# MaUWB_DSTO_v1_0.net
KiCad netlist of a schematic drawn in EAGLE
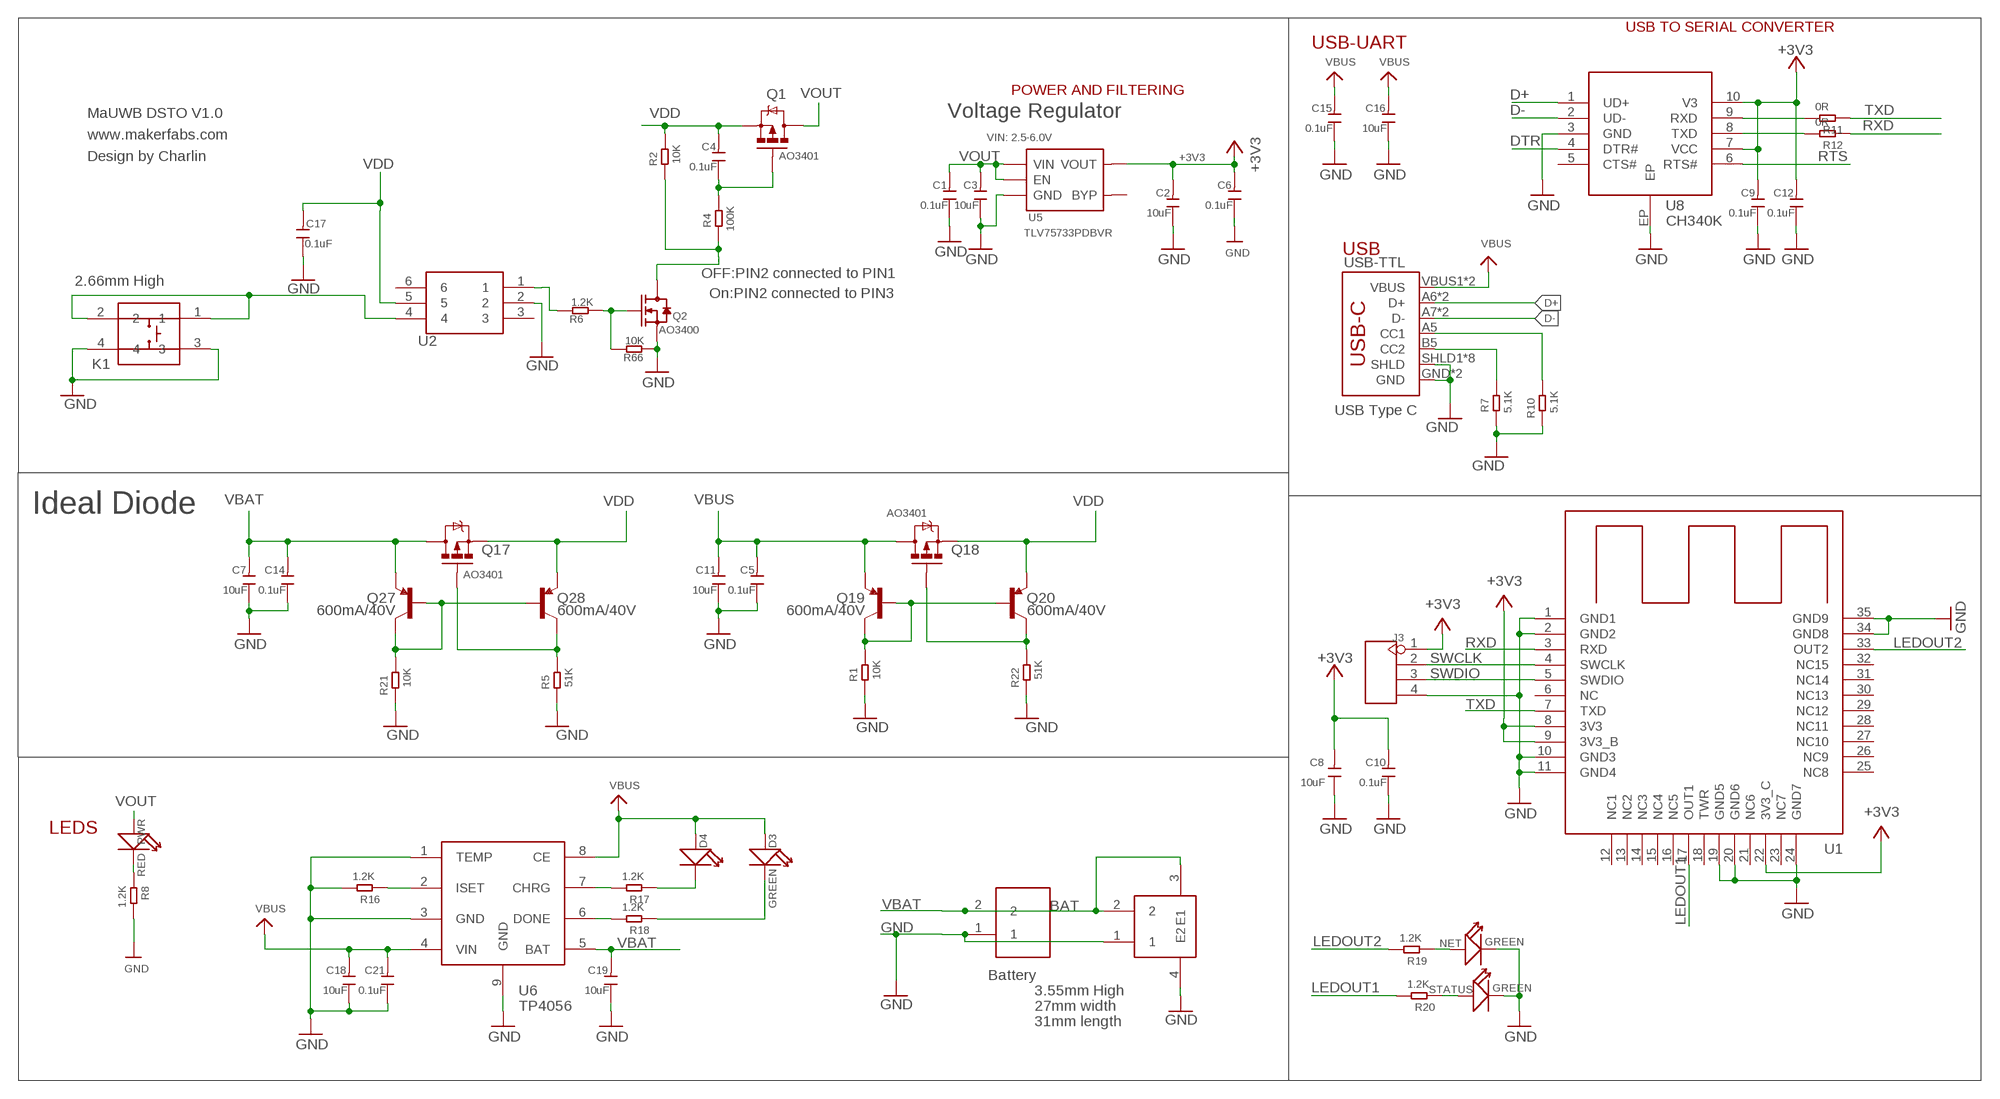
[diagram p0: schematic, sheet 1]

(export (version "E")
  (design (tool "Eeschema 10.0.6"))
  (components
    (comp (ref "BAT")
      (value "PH2.0-2P-90-DIP")
      (footprint "eagle-import:PH2.0-2P-90-DIP")
      (libsource (lib "eagle-import") (part "PH2.0-2P-90-DIP"))
    )
    (comp (ref "C1")
      (value "0.1uF")
      (footprint "eagle-import:DISCRETE_C0402")
      (libsource (lib "eagle-import") (part "DISCRETE_C-0402"))
    )
    (comp (ref "C2")
      (value "10uF")
      (footprint "eagle-import:DISCRETE_C0402")
      (libsource (lib "eagle-import") (part "DISCRETE_C-0402"))
    )
    (comp (ref "C3")
      (value "10uF")
      (footprint "eagle-import:DISCRETE_C0402")
      (libsource (lib "eagle-import") (part "DISCRETE_C-0402"))
    )
    (comp (ref "C4")
      (value "0.1uF")
      (footprint "eagle-import:DISCRETE_C0402")
      (libsource (lib "eagle-import") (part "DISCRETE_C-0402"))
    )
    (comp (ref "C5")
      (value "0.1uF")
      (footprint "eagle-import:DISCRETE_C0402")
      (libsource (lib "eagle-import") (part "DISCRETE_C-0402"))
    )
    (comp (ref "C6")
      (value "0.1uF")
      (footprint "eagle-import:DISCRETE_C0402")
      (libsource (lib "eagle-import") (part "DISCRETE_C-0402"))
    )
    (comp (ref "C7")
      (value "10uF")
      (footprint "eagle-import:DISCRETE_C0402")
      (libsource (lib "eagle-import") (part "DISCRETE_C-0402"))
    )
    (comp (ref "C8")
      (value "10uF")
      (footprint "eagle-import:DISCRETE_C0402")
      (libsource (lib "eagle-import") (part "DISCRETE_C-0402"))
    )
    (comp (ref "C9")
      (value "0.1uF")
      (footprint "eagle-import:DISCRETE_C0402")
      (libsource (lib "eagle-import") (part "DISCRETE_C-0402"))
    )
    (comp (ref "C10")
      (value "0.1uF")
      (footprint "eagle-import:DISCRETE_C0402")
      (libsource (lib "eagle-import") (part "DISCRETE_C-0402"))
    )
    (comp (ref "C11")
      (value "10uF")
      (footprint "eagle-import:DISCRETE_C0402")
      (libsource (lib "eagle-import") (part "DISCRETE_C-0402"))
    )
    (comp (ref "C12")
      (value "0.1uF")
      (footprint "eagle-import:DISCRETE_C0402")
      (libsource (lib "eagle-import") (part "DISCRETE_C-0402"))
    )
    (comp (ref "C14")
      (value "0.1uF")
      (footprint "eagle-import:DISCRETE_C0402")
      (libsource (lib "eagle-import") (part "DISCRETE_C-0402"))
    )
    (comp (ref "C15")
      (value "0.1uF")
      (footprint "eagle-import:DISCRETE_C0402")
      (libsource (lib "eagle-import") (part "DISCRETE_C-0402"))
    )
    (comp (ref "C16")
      (value "10uF")
      (footprint "eagle-import:DISCRETE_C0402")
      (libsource (lib "eagle-import") (part "DISCRETE_C-0402"))
    )
    (comp (ref "C17")
      (value "0.1uF")
      (footprint "eagle-import:DISCRETE_C0402")
      (libsource (lib "eagle-import") (part "DISCRETE_C-0402"))
    )
    (comp (ref "C18")
      (value "10uF")
      (footprint "eagle-import:DISCRETE_C0402")
      (libsource (lib "eagle-import") (part "DISCRETE_C-0402"))
    )
    (comp (ref "C19")
      (value "10uF")
      (footprint "eagle-import:DISCRETE_C0402")
      (libsource (lib "eagle-import") (part "DISCRETE_C-0402"))
    )
    (comp (ref "C21")
      (value "0.1uF")
      (footprint "eagle-import:DISCRETE_C0402")
      (libsource (lib "eagle-import") (part "DISCRETE_C-0402"))
    )
    (comp (ref "D3")
      (value "GREEN")
      (footprint "eagle-import:DISCRETE_LED-0603")
      (libsource (lib "eagle-import") (part "DISCRETE_LED0603"))
    )
    (comp (ref "D4")
      (value "DISCRETE_LED0603")
      (footprint "eagle-import:DISCRETE_LED-0603")
      (libsource (lib "eagle-import") (part "DISCRETE_LED0603"))
    )
    (comp (ref "J2")
      (value "JST-ACH1.2-2P")
      (footprint "eagle-import:A1203WRS-2P")
      (libsource (lib "eagle-import") (part "JST-ACH1.2-2P"))
    )
    (comp (ref "J3")
      (value "HEADER-4P-60/35MILROUND")
      (footprint "eagle-import:4P-65_35ROUND")
      (libsource (lib "eagle-import") (part "HEADER-4P-60/35MILROUND"))
    )
    (comp (ref "K1")
      (value "BTN01A")
      (footprint "eagle-import:BTN01A")
      (libsource (lib "eagle-import") (part "BTN01A"))
    )
    (comp (ref "NET")
      (value "GREEN")
      (footprint "eagle-import:DISCRETE_LED-0603")
      (libsource (lib "eagle-import") (part "DISCRETE_LED0603"))
    )
    (comp (ref "PWR")
      (value "RED")
      (footprint "eagle-import:DISCRETE_LED-0603")
      (libsource (lib "eagle-import") (part "DISCRETE_LED0603"))
    )
    (comp (ref "Q1")
      (value "AO3401")
      (footprint "eagle-import:SOT23-3")
      (fields (field (name "PROD_ID") "TRANS-08285"))
      (libsource (lib "eagle-import") (part "MOSFET-PCHANNEL"))
    )
    (comp (ref "Q2")
      (value "AO3400")
      (footprint "eagle-import:SOT23@1")
      (libsource (lib "eagle-import") (part "MOSFET-N'SOT23'"))
    )
    (comp (ref "Q17")
      (value "AO3401")
      (footprint "eagle-import:SOT23-3")
      (fields (field (name "PROD_ID") "TRANS-08285"))
      (libsource (lib "eagle-import") (part "MOSFET-PCHANNEL"))
    )
    (comp (ref "Q18")
      (value "AO3401")
      (footprint "eagle-import:SOT23-3")
      (fields (field (name "PROD_ID") "TRANS-08285"))
      (libsource (lib "eagle-import") (part "MOSFET-PCHANNEL"))
    )
    (comp (ref "Q19")
      (value "600mA/40V")
      (footprint "eagle-import:SOT23-3")
      (libsource (lib "eagle-import") (part "TRANS_PNP-MMBT4403"))
    )
    (comp (ref "Q20")
      (value "600mA/40V")
      (footprint "eagle-import:SOT23-3")
      (fields (field (name "PROD_ID") "TRANS-09245"))
      (libsource (lib "eagle-import") (part "TRANS_PNP-MMBT4403"))
    )
    (comp (ref "Q27")
      (value "600mA/40V")
      (footprint "eagle-import:SOT23-3")
      (libsource (lib "eagle-import") (part "TRANS_PNP-MMBT4403"))
    )
    (comp (ref "Q28")
      (value "600mA/40V")
      (footprint "eagle-import:SOT23-3")
      (fields (field (name "PROD_ID") "TRANS-09245"))
      (libsource (lib "eagle-import") (part "TRANS_PNP-MMBT4403"))
    )
    (comp (ref "R1")
      (value "10K")
      (footprint "eagle-import:DISCRETE_R0402")
      (libsource (lib "eagle-import") (part "DISCRETE_R-0402"))
    )
    (comp (ref "R2")
      (value "10K")
      (footprint "eagle-import:DISCRETE_R0402")
      (libsource (lib "eagle-import") (part "DISCRETE_R-0402"))
    )
    (comp (ref "R4")
      (value "100K")
      (footprint "eagle-import:DISCRETE_R0402")
      (libsource (lib "eagle-import") (part "DISCRETE_R-0402"))
    )
    (comp (ref "R5")
      (value "51K")
      (footprint "eagle-import:DISCRETE_R0402")
      (libsource (lib "eagle-import") (part "DISCRETE_R-0402"))
    )
    (comp (ref "R6")
      (value "1.2K")
      (footprint "eagle-import:DISCRETE_R0402")
      (libsource (lib "eagle-import") (part "DISCRETE_R-0402"))
    )
    (comp (ref "R7")
      (value "5.1K")
      (footprint "eagle-import:DISCRETE_R0402")
      (libsource (lib "eagle-import") (part "DISCRETE_R-0402"))
    )
    (comp (ref "R8")
      (value "1.2K")
      (footprint "eagle-import:DISCRETE_R0402")
      (libsource (lib "eagle-import") (part "DISCRETE_R-0402"))
    )
    (comp (ref "R10")
      (value "5.1K")
      (footprint "eagle-import:DISCRETE_R0402")
      (libsource (lib "eagle-import") (part "DISCRETE_R-0402"))
    )
    (comp (ref "R11")
      (value "0R")
      (footprint "eagle-import:DISCRETE_R0402")
      (libsource (lib "eagle-import") (part "DISCRETE_R-0402"))
    )
    (comp (ref "R12")
      (value "0R")
      (footprint "eagle-import:DISCRETE_R0402")
      (libsource (lib "eagle-import") (part "DISCRETE_R-0402"))
    )
    (comp (ref "R16")
      (value "1.2K")
      (footprint "eagle-import:DISCRETE_R0402")
      (libsource (lib "eagle-import") (part "DISCRETE_R-0402"))
    )
    (comp (ref "R17")
      (value "1.2K")
      (footprint "eagle-import:DISCRETE_R0402")
      (libsource (lib "eagle-import") (part "DISCRETE_R-0402"))
    )
    (comp (ref "R18")
      (value "1.2K")
      (footprint "eagle-import:DISCRETE_R0402")
      (libsource (lib "eagle-import") (part "DISCRETE_R-0402"))
    )
    (comp (ref "R19")
      (value "1.2K")
      (footprint "eagle-import:DISCRETE_R0402")
      (libsource (lib "eagle-import") (part "DISCRETE_R-0402"))
    )
    (comp (ref "R20")
      (value "1.2K")
      (footprint "eagle-import:DISCRETE_R0402")
      (libsource (lib "eagle-import") (part "DISCRETE_R-0402"))
    )
    (comp (ref "R21")
      (value "10K")
      (footprint "eagle-import:DISCRETE_R0402")
      (libsource (lib "eagle-import") (part "DISCRETE_R-0402"))
    )
    (comp (ref "R22")
      (value "51K")
      (footprint "eagle-import:DISCRETE_R0402")
      (libsource (lib "eagle-import") (part "DISCRETE_R-0402"))
    )
    (comp (ref "R66")
      (value "10K")
      (footprint "eagle-import:DISCRETE_R0402")
      (libsource (lib "eagle-import") (part "DISCRETE_R-0402"))
    )
    (comp (ref "STATUS")
      (value "GREEN")
      (footprint "eagle-import:DISCRETE_LED-0603")
      (libsource (lib "eagle-import") (part "DISCRETE_LED0603"))
    )
    (comp (ref "U1")
      (value "UWB-DSTO")
      (footprint "eagle-import:UWB-DSTO")
      (libsource (lib "eagle-import") (part "UWB-DSTO"))
    )
    (comp (ref "U2")
      (value "SW01A")
      (footprint "eagle-import:SOT23-6-95P-300L300W")
      (libsource (lib "eagle-import") (part "SW01A"))
    )
    (comp (ref "U5")
      (value "TLV75733PDBVR")
      (footprint "eagle-import:SOT23-5")
      (libsource (lib "eagle-import") (part "SPX3819"))
    )
    (comp (ref "U6")
      (value "TP4056")
      (footprint "eagle-import:SOP8-1.27P")
      (libsource (lib "eagle-import") (part "TP4056"))
    )
    (comp (ref "U8")
      (value "CH340K")
      (footprint "eagle-import:ESOP-10-EP-150MIL")
      (libsource (lib "eagle-import") (part "CH340K"))
    )
    (comp (ref "USB-TTL")
      (value "USB_C5")
      (footprint "eagle-import:USB-C-16P-5")
      (libsource (lib "eagle-import") (part "USB_C5"))
    )
  )
  (nets
    (net (code "1") (name "+3V3") (class "Default")
      (node (ref "C10") (pin "2") (pinfunction "2_2") (pintype "passive"))
      (node (ref "C12") (pin "2") (pinfunction "2_2") (pintype "passive"))
      (node (ref "C2") (pin "2") (pinfunction "2_2") (pintype "passive"))
      (node (ref "C6") (pin "2") (pinfunction "2_2") (pintype "passive"))
      (node (ref "C8") (pin "2") (pinfunction "2_2") (pintype "passive"))
      (node (ref "C9") (pin "2") (pinfunction "2_2") (pintype "passive"))
      (node (ref "J3") (pin "1") (pinfunction "P$1_1") (pintype "bidirectional"))
      (node (ref "U1") (pin "22") (pinfunction "3V3_C_22") (pintype "bidirectional"))
      (node (ref "U1") (pin "8") (pinfunction "3V3_8") (pintype "bidirectional"))
      (node (ref "U1") (pin "9") (pinfunction "3V3_B_9") (pintype "bidirectional"))
      (node (ref "U5") (pin "5") (pinfunction "VOUT_5") (pintype "bidirectional"))
      (node (ref "U8") (pin "10") (pinfunction "V3_10") (pintype "bidirectional"))
      (node (ref "U8") (pin "7") (pinfunction "VCC_7") (pintype "bidirectional"))
    )
    (net (code "2") (name "/DTR") (class "Default")
      (node (ref "U8") (pin "4") (pinfunction "DTR#_4") (pintype "bidirectional"))
    )
    (net (code "3") (name "/LEDOUT1") (class "Default")
      (node (ref "R20") (pin "2") (pinfunction "2_2") (pintype "passive"))
      (node (ref "U1") (pin "17") (pinfunction "OUT1_17") (pintype "bidirectional"))
    )
    (net (code "4") (name "/LEDOUT2") (class "Default")
      (node (ref "R19") (pin "2") (pinfunction "2_2") (pintype "passive"))
      (node (ref "U1") (pin "33") (pinfunction "OUT2_33") (pintype "bidirectional"))
    )
    (net (code "5") (name "/RTS") (class "Default")
      (node (ref "U8") (pin "6") (pinfunction "RTS#_6") (pintype "bidirectional"))
    )
    (net (code "6") (name "/RXD") (class "Default")
      (node (ref "R12") (pin "1") (pinfunction "1_1") (pintype "passive"))
      (node (ref "U1") (pin "3") (pinfunction "RXD_3") (pintype "bidirectional"))
    )
    (net (code "7") (name "/SWCLK") (class "Default")
      (node (ref "J3") (pin "2") (pinfunction "P$2_2") (pintype "bidirectional"))
      (node (ref "U1") (pin "4") (pinfunction "SWCLK_4") (pintype "bidirectional"))
    )
    (net (code "8") (name "/SWDIO") (class "Default")
      (node (ref "J3") (pin "3") (pinfunction "P$3_3") (pintype "bidirectional"))
      (node (ref "U1") (pin "5") (pinfunction "SWDIO_5") (pintype "bidirectional"))
    )
    (net (code "9") (name "/TXD") (class "Default")
      (node (ref "R11") (pin "1") (pinfunction "1_1") (pintype "passive"))
      (node (ref "U1") (pin "7") (pinfunction "TXD_7") (pintype "bidirectional"))
    )
    (net (code "10") (name "/VBAT") (class "Default")
      (node (ref "BAT") (pin "2") (pinfunction "2_2") (pintype "bidirectional"))
      (node (ref "C14") (pin "2") (pinfunction "2_2") (pintype "passive"))
      (node (ref "C19") (pin "2") (pinfunction "2_2") (pintype "passive"))
      (node (ref "C7") (pin "2") (pinfunction "2_2") (pintype "passive"))
      (node (ref "J2") (pin "2") (pinfunction "2_2") (pintype "bidirectional"))
      (node (ref "J2") (pin "3") (pinfunction "E1_3") (pintype "bidirectional"))
      (node (ref "Q17") (pin "3") (pinfunction "D_3") (pintype "passive"))
      (node (ref "Q27") (pin "2") (pinfunction "E_2") (pintype "passive"))
      (node (ref "U6") (pin "5") (pinfunction "BAT_5") (pintype "bidirectional"))
    )
    (net (code "11") (name "/VDD") (class "Default")
      (node (ref "C17") (pin "2") (pinfunction "2_2") (pintype "passive"))
      (node (ref "C4") (pin "2") (pinfunction "2_2") (pintype "passive"))
      (node (ref "Q1") (pin "2") (pinfunction "S_2") (pintype "passive"))
      (node (ref "Q17") (pin "2") (pinfunction "S_2") (pintype "passive"))
      (node (ref "Q18") (pin "2") (pinfunction "S_2") (pintype "passive"))
      (node (ref "Q20") (pin "2") (pinfunction "E_2") (pintype "passive"))
      (node (ref "Q28") (pin "2") (pinfunction "E_2") (pintype "passive"))
      (node (ref "R2") (pin "2") (pinfunction "2_2") (pintype "passive"))
      (node (ref "U2") (pin "5") (pinfunction "5_5") (pintype "bidirectional"))
    )
    (net (code "12") (name "/VOUT") (class "Default")
      (node (ref "C1") (pin "2") (pinfunction "2_2") (pintype "passive"))
      (node (ref "C3") (pin "2") (pinfunction "2_2") (pintype "passive"))
      (node (ref "PWR") (pin "+") (pinfunction "+_+") (pintype "passive"))
      (node (ref "Q1") (pin "3") (pinfunction "D_3") (pintype "passive"))
      (node (ref "U5") (pin "1") (pinfunction "VIN_1") (pintype "bidirectional"))
      (node (ref "U5") (pin "3") (pinfunction "EN_3") (pintype "bidirectional"))
    )
    (net (code "13") (name "D+") (class "Default")
      (node (ref "U8") (pin "1") (pinfunction "UD+_1") (pintype "bidirectional"))
      (node (ref "USB-TTL") (pin "A6") (pinfunction "D+_A6") (pintype "bidirectional"))
      (node (ref "USB-TTL") (pin "B6") (pinfunction "D+_B6") (pintype "bidirectional"))
    )
    (net (code "14") (name "D-") (class "Default")
      (node (ref "U8") (pin "2") (pinfunction "UD-_2") (pintype "bidirectional"))
      (node (ref "USB-TTL") (pin "A7") (pinfunction "D-_A7") (pintype "bidirectional"))
      (node (ref "USB-TTL") (pin "B7") (pinfunction "D-_B7") (pintype "bidirectional"))
    )
    (net (code "15") (name "GND") (class "Default")
      (node (ref "BAT") (pin "1") (pinfunction "1_1") (pintype "bidirectional"))
      (node (ref "C1") (pin "1") (pinfunction "1_1") (pintype "passive"))
      (node (ref "C10") (pin "1") (pinfunction "1_1") (pintype "passive"))
      (node (ref "C11") (pin "1") (pinfunction "1_1") (pintype "passive"))
      (node (ref "C12") (pin "1") (pinfunction "1_1") (pintype "passive"))
      (node (ref "C14") (pin "1") (pinfunction "1_1") (pintype "passive"))
      (node (ref "C15") (pin "1") (pinfunction "1_1") (pintype "passive"))
      (node (ref "C16") (pin "1") (pinfunction "1_1") (pintype "passive"))
      (node (ref "C17") (pin "1") (pinfunction "1_1") (pintype "passive"))
      (node (ref "C18") (pin "1") (pinfunction "1_1") (pintype "passive"))
      (node (ref "C19") (pin "1") (pinfunction "1_1") (pintype "passive"))
      (node (ref "C2") (pin "1") (pinfunction "1_1") (pintype "passive"))
      (node (ref "C21") (pin "1") (pinfunction "1_1") (pintype "passive"))
      (node (ref "C3") (pin "1") (pinfunction "1_1") (pintype "passive"))
      (node (ref "C5") (pin "1") (pinfunction "1_1") (pintype "passive"))
      (node (ref "C6") (pin "1") (pinfunction "1_1") (pintype "passive"))
      (node (ref "C7") (pin "1") (pinfunction "1_1") (pintype "passive"))
      (node (ref "C8") (pin "1") (pinfunction "1_1") (pintype "passive"))
      (node (ref "C9") (pin "1") (pinfunction "1_1") (pintype "passive"))
      (node (ref "J2") (pin "1") (pinfunction "1_1") (pintype "bidirectional"))
      (node (ref "J2") (pin "4") (pinfunction "E2_4") (pintype "bidirectional"))
      (node (ref "J3") (pin "4") (pinfunction "P$4_4") (pintype "bidirectional"))
      (node (ref "K1") (pin "3") (pinfunction "3_3") (pintype "bidirectional"))
      (node (ref "K1") (pin "4") (pinfunction "4_4") (pintype "bidirectional"))
      (node (ref "NET") (pin "-") (pinfunction "-_-") (pintype "passive"))
      (node (ref "Q2") (pin "2") (pinfunction "S_2") (pintype "passive"))
      (node (ref "R1") (pin "1") (pinfunction "1_1") (pintype "passive"))
      (node (ref "R10") (pin "1") (pinfunction "1_1") (pintype "passive"))
      (node (ref "R16") (pin "2") (pinfunction "2_2") (pintype "passive"))
      (node (ref "R21") (pin "1") (pinfunction "1_1") (pintype "passive"))
      (node (ref "R22") (pin "1") (pinfunction "1_1") (pintype "passive"))
      (node (ref "R5") (pin "1") (pinfunction "1_1") (pintype "passive"))
      (node (ref "R66") (pin "1") (pinfunction "1_1") (pintype "passive"))
      (node (ref "R7") (pin "1") (pinfunction "1_1") (pintype "passive"))
      (node (ref "R8") (pin "2") (pinfunction "2_2") (pintype "passive"))
      (node (ref "STATUS") (pin "-") (pinfunction "-_-") (pintype "passive"))
      (node (ref "U1") (pin "1") (pinfunction "GND1_1") (pintype "bidirectional"))
      (node (ref "U1") (pin "10") (pinfunction "GND3_10") (pintype "bidirectional"))
      (node (ref "U1") (pin "11") (pinfunction "GND4_11") (pintype "bidirectional"))
      (node (ref "U1") (pin "19") (pinfunction "GND5_19") (pintype "bidirectional"))
      (node (ref "U1") (pin "2") (pinfunction "GND2_2") (pintype "bidirectional"))
      (node (ref "U1") (pin "20") (pinfunction "GND6_20") (pintype "bidirectional"))
      (node (ref "U1") (pin "24") (pinfunction "GND7_24") (pintype "bidirectional"))
      (node (ref "U1") (pin "34") (pinfunction "GND8_34") (pintype "bidirectional"))
      (node (ref "U1") (pin "35") (pinfunction "GND9_35") (pintype "bidirectional"))
      (node (ref "U2") (pin "2") (pinfunction "2_2") (pintype "bidirectional"))
      (node (ref "U5") (pin "2") (pinfunction "GND_2") (pintype "bidirectional"))
      (node (ref "U6") (pin "1") (pinfunction "TEMP_1") (pintype "bidirectional"))
      (node (ref "U6") (pin "3") (pinfunction "GND_3") (pintype "bidirectional"))
      (node (ref "U6") (pin "9") (pinfunction "GND_9") (pintype "bidirectional"))
      (node (ref "U8") (pin "3") (pinfunction "GND_3") (pintype "bidirectional"))
      (node (ref "U8") (pin "EP") (pinfunction "EP_EP") (pintype "bidirectional"))
      (node (ref "USB-TTL") (pin "GND") (pinfunction "GND_GND") (pintype "bidirectional"))
      (node (ref "USB-TTL") (pin "GND2") (pinfunction "GND_GND2") (pintype "bidirectional"))
      (node (ref "USB-TTL") (pin "SHLD1") (pinfunction "SHLD_SHLD1") (pintype "bidirectional"))
      (node (ref "USB-TTL") (pin "SHLD2") (pinfunction "SHLD_SHLD2") (pintype "bidirectional"))
      (node (ref "USB-TTL") (pin "SHLD3") (pinfunction "SHLD_SHLD3") (pintype "bidirectional"))
      (node (ref "USB-TTL") (pin "SHLD4") (pinfunction "SHLD_SHLD4") (pintype "bidirectional"))
      (node (ref "USB-TTL") (pin "SHLD5") (pinfunction "SHLD_SHLD5") (pintype "bidirectional"))
      (node (ref "USB-TTL") (pin "SHLD6") (pinfunction "SHLD_SHLD6") (pintype "bidirectional"))
      (node (ref "USB-TTL") (pin "SHLD7") (pinfunction "SHLD_SHLD7") (pintype "bidirectional"))
      (node (ref "USB-TTL") (pin "SHLD8") (pinfunction "SHLD_SHLD8") (pintype "bidirectional"))
    )
    (net (code "16") (name "Net-(D3-Pad-)") (class "Default")
      (node (ref "D3") (pin "-") (pinfunction "-_-") (pintype "passive"))
      (node (ref "R18") (pin "1") (pinfunction "1_1") (pintype "passive"))
    )
    (net (code "17") (name "Net-(D4-Pad-)") (class "Default")
      (node (ref "D4") (pin "-") (pinfunction "-_-") (pintype "passive"))
      (node (ref "R17") (pin "1") (pinfunction "1_1") (pintype "passive"))
    )
    (net (code "18") (name "Net-(K1-Pad1)") (class "Default")
      (node (ref "K1") (pin "1") (pinfunction "1_1") (pintype "bidirectional"))
      (node (ref "K1") (pin "2") (pinfunction "2_2") (pintype "bidirectional"))
      (node (ref "U2") (pin "4") (pinfunction "4_4") (pintype "bidirectional"))
    )
    (net (code "19") (name "Net-(NET-Pad+)") (class "Default")
      (node (ref "NET") (pin "+") (pinfunction "+_+") (pintype "passive"))
      (node (ref "R19") (pin "1") (pinfunction "1_1") (pintype "passive"))
    )
    (net (code "20") (name "Net-(PWR-Pad-)") (class "Default")
      (node (ref "PWR") (pin "-") (pinfunction "-_-") (pintype "passive"))
      (node (ref "R8") (pin "1") (pinfunction "1_1") (pintype "passive"))
    )
    (net (code "21") (name "Net-(Q1-G)") (class "Default")
      (node (ref "C4") (pin "1") (pinfunction "1_1") (pintype "passive"))
      (node (ref "Q1") (pin "1") (pinfunction "G_1") (pintype "passive"))
      (node (ref "R4") (pin "2") (pinfunction "2_2") (pintype "passive"))
    )
    (net (code "22") (name "Net-(Q2-D)") (class "Default")
      (node (ref "Q2") (pin "3") (pinfunction "D_3") (pintype "passive"))
      (node (ref "R2") (pin "1") (pinfunction "1_1") (pintype "passive"))
      (node (ref "R4") (pin "1") (pinfunction "1_1") (pintype "passive"))
    )
    (net (code "23") (name "Net-(Q2-G)") (class "Default")
      (node (ref "Q2") (pin "1") (pinfunction "G_1") (pintype "passive"))
      (node (ref "R6") (pin "1") (pinfunction "1_1") (pintype "passive"))
      (node (ref "R66") (pin "2") (pinfunction "2_2") (pintype "passive"))
    )
    (net (code "24") (name "Net-(Q17-G)") (class "Default")
      (node (ref "Q17") (pin "1") (pinfunction "G_1") (pintype "passive"))
      (node (ref "Q28") (pin "3") (pinfunction "C_3") (pintype "passive"))
      (node (ref "R5") (pin "2") (pinfunction "2_2") (pintype "passive"))
    )
    (net (code "25") (name "Net-(Q18-G)") (class "Default")
      (node (ref "Q18") (pin "1") (pinfunction "G_1") (pintype "passive"))
      (node (ref "Q20") (pin "3") (pinfunction "C_3") (pintype "passive"))
      (node (ref "R22") (pin "2") (pinfunction "2_2") (pintype "passive"))
    )
    (net (code "26") (name "Net-(Q19-B)") (class "Default")
      (node (ref "Q19") (pin "1") (pinfunction "B_1") (pintype "passive"))
      (node (ref "Q19") (pin "3") (pinfunction "C_3") (pintype "passive"))
      (node (ref "Q20") (pin "1") (pinfunction "B_1") (pintype "passive"))
      (node (ref "R1") (pin "2") (pinfunction "2_2") (pintype "passive"))
    )
    (net (code "27") (name "Net-(Q27-B)") (class "Default")
      (node (ref "Q27") (pin "1") (pinfunction "B_1") (pintype "passive"))
      (node (ref "Q27") (pin "3") (pinfunction "C_3") (pintype "passive"))
      (node (ref "Q28") (pin "1") (pinfunction "B_1") (pintype "passive"))
      (node (ref "R21") (pin "2") (pinfunction "2_2") (pintype "passive"))
    )
    (net (code "28") (name "Net-(R6-Pad2)") (class "Default")
      (node (ref "R6") (pin "2") (pinfunction "2_2") (pintype "passive"))
      (node (ref "U2") (pin "1") (pinfunction "1_1") (pintype "bidirectional"))
    )
    (net (code "29") (name "Net-(R20-Pad1)") (class "Default")
      (node (ref "R20") (pin "1") (pinfunction "1_1") (pintype "passive"))
      (node (ref "STATUS") (pin "+") (pinfunction "+_+") (pintype "passive"))
    )
    (net (code "30") (name "Net-(U6-CHRG)") (class "Default")
      (node (ref "R17") (pin "2") (pinfunction "2_2") (pintype "passive"))
      (node (ref "U6") (pin "7") (pinfunction "CHRG_7") (pintype "bidirectional"))
    )
    (net (code "31") (name "Net-(U6-DONE)") (class "Default")
      (node (ref "R18") (pin "2") (pinfunction "2_2") (pintype "passive"))
      (node (ref "U6") (pin "6") (pinfunction "DONE_6") (pintype "bidirectional"))
    )
    (net (code "32") (name "Net-(U6-ISET)") (class "Default")
      (node (ref "R16") (pin "1") (pinfunction "1_1") (pintype "passive"))
      (node (ref "U6") (pin "2") (pinfunction "ISET_2") (pintype "bidirectional"))
    )
    (net (code "33") (name "Net-(U8-RXD)") (class "Default")
      (node (ref "R11") (pin "2") (pinfunction "2_2") (pintype "passive"))
      (node (ref "U8") (pin "9") (pinfunction "RXD_9") (pintype "bidirectional"))
    )
    (net (code "34") (name "Net-(U8-TXD)") (class "Default")
      (node (ref "R12") (pin "2") (pinfunction "2_2") (pintype "passive"))
      (node (ref "U8") (pin "8") (pinfunction "TXD_8") (pintype "bidirectional"))
    )
    (net (code "35") (name "Net-(USB-TTL-CC1)") (class "Default")
      (node (ref "R10") (pin "2") (pinfunction "2_2") (pintype "passive"))
      (node (ref "USB-TTL") (pin "A5") (pinfunction "CC1_A5") (pintype "bidirectional"))
    )
    (net (code "36") (name "Net-(USB-TTL-CC2)") (class "Default")
      (node (ref "R7") (pin "2") (pinfunction "2_2") (pintype "passive"))
      (node (ref "USB-TTL") (pin "B5") (pinfunction "CC2_B5") (pintype "bidirectional"))
    )
    (net (code "37") (name "VBUS") (class "Default")
      (node (ref "C11") (pin "2") (pinfunction "2_2") (pintype "passive"))
      (node (ref "C15") (pin "2") (pinfunction "2_2") (pintype "passive"))
      (node (ref "C16") (pin "2") (pinfunction "2_2") (pintype "passive"))
      (node (ref "C18") (pin "2") (pinfunction "2_2") (pintype "passive"))
      (node (ref "C21") (pin "2") (pinfunction "2_2") (pintype "passive"))
      (node (ref "C5") (pin "2") (pinfunction "2_2") (pintype "passive"))
      (node (ref "D3") (pin "+") (pinfunction "+_+") (pintype "passive"))
      (node (ref "D4") (pin "+") (pinfunction "+_+") (pintype "passive"))
      (node (ref "Q18") (pin "3") (pinfunction "D_3") (pintype "passive"))
      (node (ref "Q19") (pin "2") (pinfunction "E_2") (pintype "passive"))
      (node (ref "U6") (pin "4") (pinfunction "VIN_4") (pintype "bidirectional"))
      (node (ref "U6") (pin "8") (pinfunction "CE_8") (pintype "bidirectional"))
      (node (ref "USB-TTL") (pin "VBUS1") (pinfunction "VBUS_VBUS1") (pintype "bidirectional"))
      (node (ref "USB-TTL") (pin "VBUS2") (pinfunction "VBUS_VBUS2") (pintype "bidirectional"))
    )
    (net (code "38") (name "unconnected-(U1-NC-Pad6)") (class "Default")
      (node (ref "U1") (pin "6") (pinfunction "NC_6") (pintype "bidirectional"))
    )
    (net (code "39") (name "unconnected-(U1-NC1-Pad12)") (class "Default")
      (node (ref "U1") (pin "12") (pinfunction "NC1_12") (pintype "bidirectional"))
    )
    (net (code "40") (name "unconnected-(U1-NC2-Pad13)") (class "Default")
      (node (ref "U1") (pin "13") (pinfunction "NC2_13") (pintype "bidirectional"))
    )
    (net (code "41") (name "unconnected-(U1-NC3-Pad14)") (class "Default")
      (node (ref "U1") (pin "14") (pinfunction "NC3_14") (pintype "bidirectional"))
    )
    (net (code "42") (name "unconnected-(U1-NC4-Pad15)") (class "Default")
      (node (ref "U1") (pin "15") (pinfunction "NC4_15") (pintype "bidirectional"))
    )
    (net (code "43") (name "unconnected-(U1-NC5-Pad16)") (class "Default")
      (node (ref "U1") (pin "16") (pinfunction "NC5_16") (pintype "bidirectional"))
    )
    (net (code "44") (name "unconnected-(U1-NC6-Pad21)") (class "Default")
      (node (ref "U1") (pin "21") (pinfunction "NC6_21") (pintype "bidirectional"))
    )
    (net (code "45") (name "unconnected-(U1-NC7-Pad23)") (class "Default")
      (node (ref "U1") (pin "23") (pinfunction "NC7_23") (pintype "bidirectional"))
    )
    (net (code "46") (name "unconnected-(U1-NC8-Pad25)") (class "Default")
      (node (ref "U1") (pin "25") (pinfunction "NC8_25") (pintype "bidirectional"))
    )
    (net (code "47") (name "unconnected-(U1-NC9-Pad26)") (class "Default")
      (node (ref "U1") (pin "26") (pinfunction "NC9_26") (pintype "bidirectional"))
    )
    (net (code "48") (name "unconnected-(U1-NC10-Pad27)") (class "Default")
      (node (ref "U1") (pin "27") (pinfunction "NC10_27") (pintype "bidirectional"))
    )
    (net (code "49") (name "unconnected-(U1-NC11-Pad28)") (class "Default")
      (node (ref "U1") (pin "28") (pinfunction "NC11_28") (pintype "bidirectional"))
    )
    (net (code "50") (name "unconnected-(U1-NC12-Pad29)") (class "Default")
      (node (ref "U1") (pin "29") (pinfunction "NC12_29") (pintype "bidirectional"))
    )
    (net (code "51") (name "unconnected-(U1-NC13-Pad30)") (class "Default")
      (node (ref "U1") (pin "30") (pinfunction "NC13_30") (pintype "bidirectional"))
    )
    (net (code "52") (name "unconnected-(U1-NC14-Pad31)") (class "Default")
      (node (ref "U1") (pin "31") (pinfunction "NC14_31") (pintype "bidirectional"))
    )
    (net (code "53") (name "unconnected-(U1-NC15-Pad32)") (class "Default")
      (node (ref "U1") (pin "32") (pinfunction "NC15_32") (pintype "bidirectional"))
    )
    (net (code "54") (name "unconnected-(U1-TWR-Pad18)") (class "Default")
      (node (ref "U1") (pin "18") (pinfunction "TWR_18") (pintype "bidirectional"))
    )
    (net (code "55") (name "unconnected-(U2-Pad3)") (class "Default")
      (node (ref "U2") (pin "3") (pinfunction "3_3") (pintype "bidirectional"))
    )
    (net (code "56") (name "unconnected-(U2-Pad6)") (class "Default")
      (node (ref "U2") (pin "6") (pinfunction "6_6") (pintype "bidirectional"))
    )
    (net (code "57") (name "unconnected-(U5-BYP-Pad4)") (class "Default")
      (node (ref "U5") (pin "4") (pinfunction "BYP_4") (pintype "bidirectional"))
    )
    (net (code "58") (name "unconnected-(U8-CTS#-Pad5)") (class "Default")
      (node (ref "U8") (pin "5") (pinfunction "CTS#_5") (pintype "bidirectional"))
    )
  )
)
